# rapidshark-main-breakout-top-mk-1_9.net
KiCad netlist of a schematic drawn in EAGLE
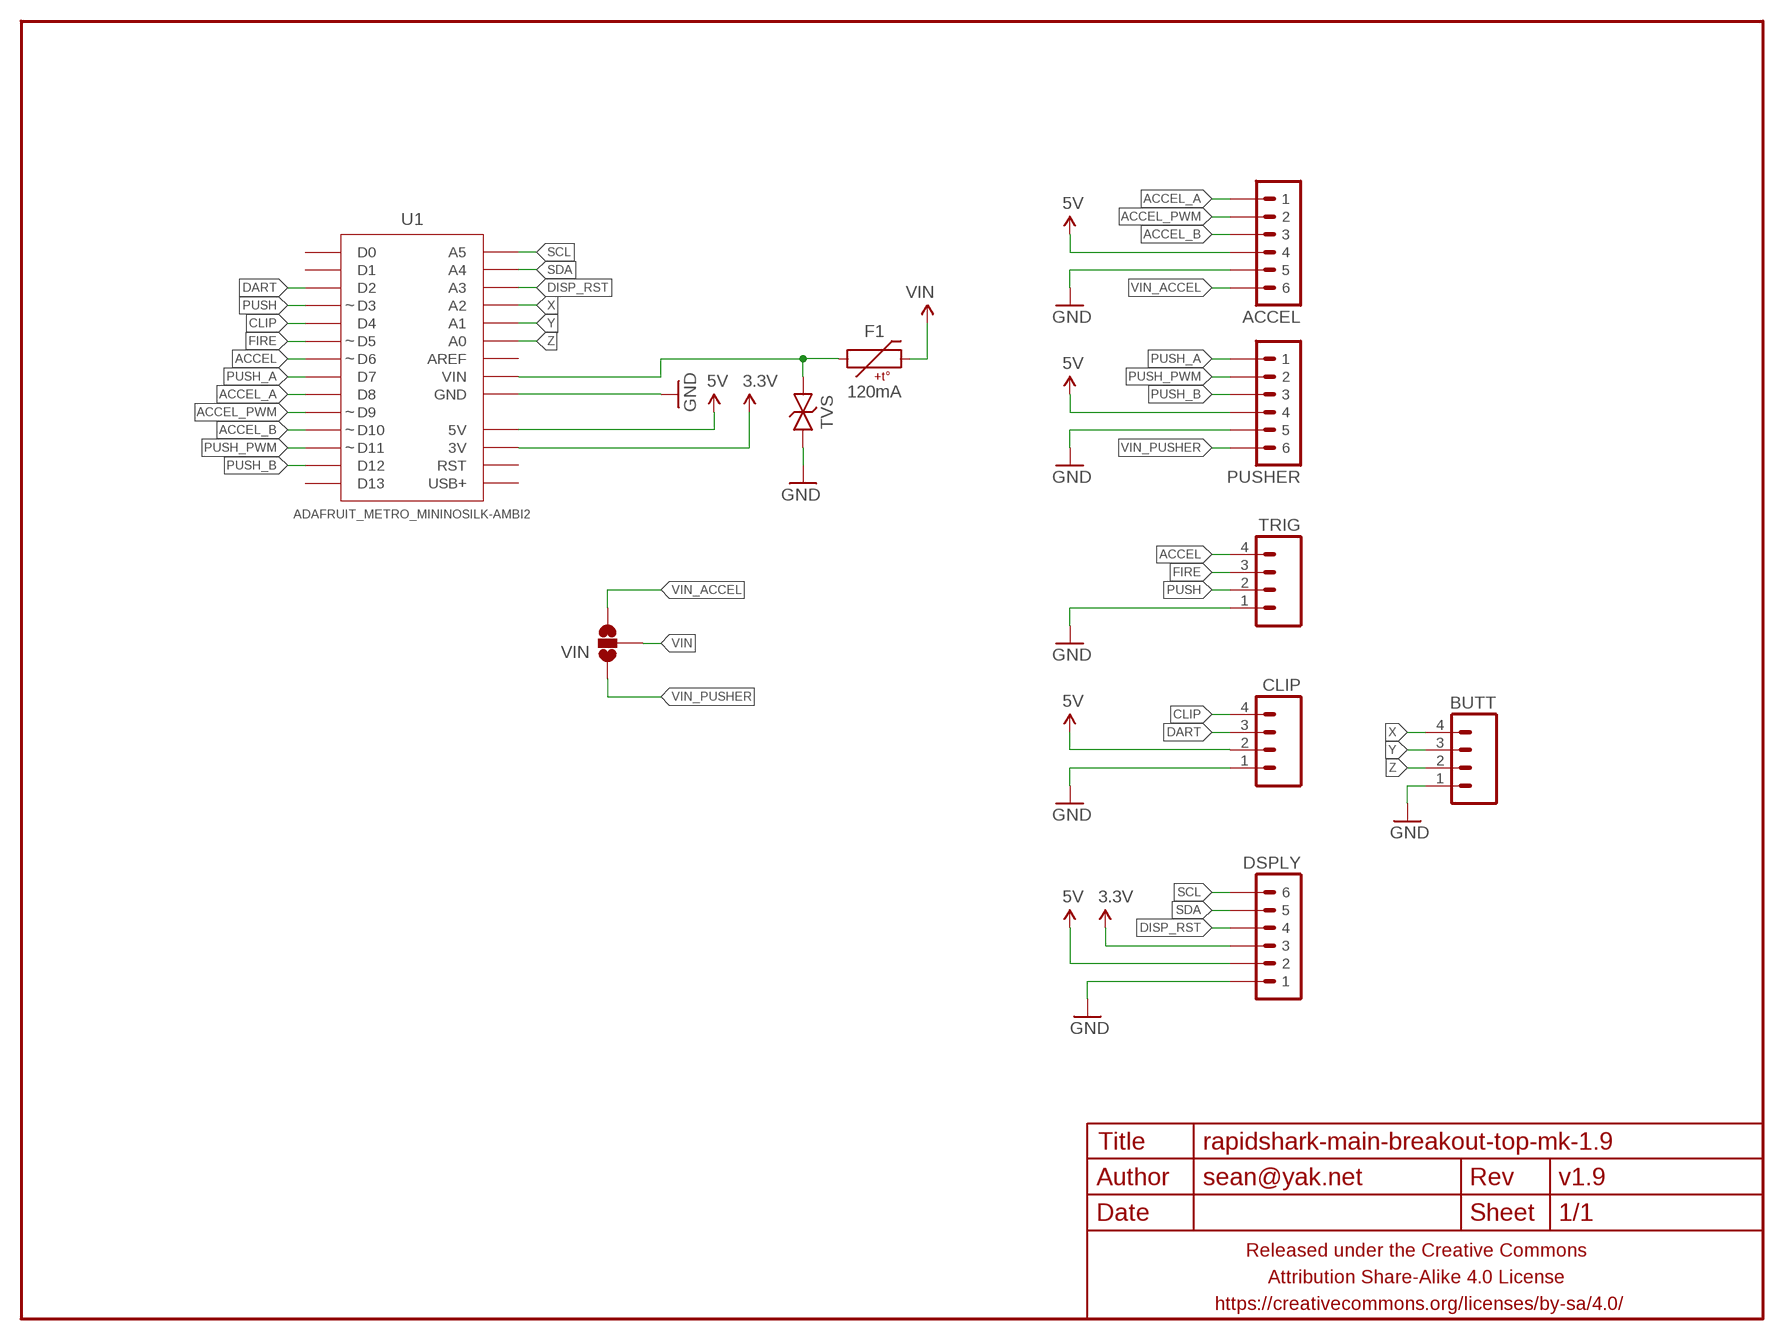
[diagram p0: schematic, sheet 1]

(export (version "E")
  (design (tool "Eeschema 10.0.6"))
  (components
    (comp (ref "ACCEL")
      (value "M06JST-PH-PTH-VERT")
      (footprint "eagle-import:JST-6-PH-VERT-PTH")
      (libsource (lib "eagle-import") (part "M06JST-PH-PTH-VERT"))
    )
    (comp (ref "BUTT")
      (value "M04JST-PTH-VERT")
      (footprint "eagle-import:JST-4-PH-VERT-PTH")
      (libsource (lib "eagle-import") (part "M04JST-PTH-VERT"))
    )
    (comp (ref "CLIP")
      (value "M04JST-PTH-VERT")
      (footprint "eagle-import:JST-4-PH-VERT-PTH")
      (libsource (lib "eagle-import") (part "M04JST-PTH-VERT"))
    )
    (comp (ref "DSPLY")
      (value "M06JST-PH-PTH-VERT")
      (footprint "eagle-import:JST-6-PH-VERT-PTH")
      (libsource (lib "eagle-import") (part "M06JST-PH-PTH-VERT"))
    )
    (comp (ref "F1")
      (value "120mA")
      (footprint "eagle-import:PTC-1206")
      (libsource (lib "eagle-import") (part "PTCSMD"))
    )
    (comp (ref "FRAME1")
      (value "FRAME-LETTERNO_PACKAGE")
      (footprint "eagle-import:DUMMY")
      (fields (field (name "DESIGNER") "sean@yak.net") (field (name "VERSION") "v1.9"))
      (libsource (lib "eagle-import") (part "FRAME-LETTERNO_PACKAGE"))
    )
    (comp (ref "PUSHER")
      (value "M06JST-PH-PTH-VERT")
      (footprint "eagle-import:JST-6-PH-VERT-PTH")
      (libsource (lib "eagle-import") (part "M06JST-PH-PTH-VERT"))
    )
    (comp (ref "TRIG")
      (value "M04JST-PTH-VERT")
      (footprint "eagle-import:JST-4-PH-VERT-PTH")
      (libsource (lib "eagle-import") (part "M04JST-PTH-VERT"))
    )
    (comp (ref "TVS")
      (value "TVSSMA")
      (footprint "eagle-import:SMA-DIODE-TVS-BIDIR")
      (libsource (lib "eagle-import") (part "TVSSMA"))
    )
    (comp (ref "U1")
      (value "ADAFRUIT_METRO_MININOSILK-AMBI2")
      (footprint "eagle-import:ADAFRUIT_METRO_MINI_BACK")
      (libsource (lib "eagle-import") (part "ADAFRUIT_METRO_MININOSILK-AMBI2"))
    )
    (comp (ref "VIN")
      (value "JUMPER-PAD-3-NOFULL_BOX_SILK")
      (footprint "eagle-import:PAD-JUMPER-3-NO_YES_SILK_FULL_BOX")
      (libsource (lib "eagle-import") (part "JUMPER-PAD-3-NOFULL_BOX_SILK"))
    )
  )
  (nets
    (net (code "1") (name "3.3V") (class "Default")
      (node (ref "DSPLY") (pin "3") (pinfunction "3_3") (pintype "passive"))
      (node (ref "U1") (pin "17") (pinfunction "3V_17") (pintype "bidirectional"))
    )
    (net (code "2") (name "5V") (class "Default")
      (node (ref "ACCEL") (pin "4") (pinfunction "4_4") (pintype "passive"))
      (node (ref "CLIP") (pin "2") (pinfunction "2_2") (pintype "passive"))
      (node (ref "DSPLY") (pin "2") (pinfunction "2_2") (pintype "passive"))
      (node (ref "PUSHER") (pin "4") (pinfunction "4_4") (pintype "passive"))
      (node (ref "U1") (pin "18") (pinfunction "5V_18") (pintype "bidirectional"))
    )
    (net (code "3") (name "ACCEL") (class "Default")
      (node (ref "TRIG") (pin "4") (pinfunction "4_4") (pintype "passive"))
      (node (ref "U1") (pin "7") (pinfunction "D6_7") (pintype "bidirectional"))
    )
    (net (code "4") (name "ACCEL_A") (class "Default")
      (node (ref "ACCEL") (pin "1") (pinfunction "1_1") (pintype "passive"))
      (node (ref "U1") (pin "9") (pinfunction "D8_9") (pintype "bidirectional"))
    )
    (net (code "5") (name "ACCEL_B") (class "Default")
      (node (ref "ACCEL") (pin "3") (pinfunction "3_3") (pintype "passive"))
      (node (ref "U1") (pin "11") (pinfunction "D10_11") (pintype "bidirectional"))
    )
    (net (code "6") (name "ACCEL_PWM") (class "Default")
      (node (ref "ACCEL") (pin "2") (pinfunction "2_2") (pintype "passive"))
      (node (ref "U1") (pin "10") (pinfunction "D9_10") (pintype "bidirectional"))
    )
    (net (code "7") (name "CLIP") (class "Default")
      (node (ref "CLIP") (pin "4") (pinfunction "4_4") (pintype "passive"))
      (node (ref "U1") (pin "5") (pinfunction "D4_5") (pintype "bidirectional"))
    )
    (net (code "8") (name "DART") (class "Default")
      (node (ref "CLIP") (pin "3") (pinfunction "3_3") (pintype "passive"))
      (node (ref "U1") (pin "3") (pinfunction "D2_3") (pintype "bidirectional"))
    )
    (net (code "9") (name "DISP_RST") (class "Default")
      (node (ref "DSPLY") (pin "4") (pinfunction "4_4") (pintype "passive"))
      (node (ref "U1") (pin "26") (pinfunction "A3_26") (pintype "bidirectional"))
    )
    (net (code "10") (name "FIRE") (class "Default")
      (node (ref "TRIG") (pin "3") (pinfunction "3_3") (pintype "passive"))
      (node (ref "U1") (pin "6") (pinfunction "D5_6") (pintype "bidirectional"))
    )
    (net (code "11") (name "GND") (class "Default")
      (node (ref "ACCEL") (pin "5") (pinfunction "5_5") (pintype "passive"))
      (node (ref "BUTT") (pin "1") (pinfunction "1_1") (pintype "passive"))
      (node (ref "CLIP") (pin "1") (pinfunction "1_1") (pintype "passive"))
      (node (ref "DSPLY") (pin "1") (pinfunction "1_1") (pintype "passive"))
      (node (ref "PUSHER") (pin "5") (pinfunction "5_5") (pintype "passive"))
      (node (ref "TRIG") (pin "1") (pinfunction "1_1") (pintype "passive"))
      (node (ref "TVS") (pin "1") (pinfunction "1_1") (pintype "passive"))
      (node (ref "U1") (pin "19") (pinfunction "GND_19") (pintype "bidirectional"))
      (node (ref "U1") (pin "20") (pinfunction "GND_20") (pintype "bidirectional"))
    )
    (net (code "12") (name "Net-(U1-VIN)") (class "Default")
      (node (ref "F1") (pin "1") (pinfunction "1_1") (pintype "passive"))
      (node (ref "TVS") (pin "2") (pinfunction "2_2") (pintype "passive"))
      (node (ref "U1") (pin "21") (pinfunction "VIN_21") (pintype "bidirectional"))
    )
    (net (code "13") (name "PUSH") (class "Default")
      (node (ref "TRIG") (pin "2") (pinfunction "2_2") (pintype "passive"))
      (node (ref "U1") (pin "4") (pinfunction "D3_4") (pintype "bidirectional"))
    )
    (net (code "14") (name "PUSH_A") (class "Default")
      (node (ref "PUSHER") (pin "1") (pinfunction "1_1") (pintype "passive"))
      (node (ref "U1") (pin "8") (pinfunction "D7_8") (pintype "bidirectional"))
    )
    (net (code "15") (name "PUSH_B") (class "Default")
      (node (ref "PUSHER") (pin "3") (pinfunction "3_3") (pintype "passive"))
      (node (ref "U1") (pin "13") (pinfunction "D12_13") (pintype "bidirectional"))
    )
    (net (code "16") (name "PUSH_PWM") (class "Default")
      (node (ref "PUSHER") (pin "2") (pinfunction "2_2") (pintype "passive"))
      (node (ref "U1") (pin "12") (pinfunction "D11_12") (pintype "bidirectional"))
    )
    (net (code "17") (name "SCL") (class "Default")
      (node (ref "DSPLY") (pin "6") (pinfunction "6_6") (pintype "passive"))
      (node (ref "U1") (pin "28") (pinfunction "A5_28") (pintype "bidirectional"))
    )
    (net (code "18") (name "SDA") (class "Default")
      (node (ref "DSPLY") (pin "5") (pinfunction "5_5") (pintype "passive"))
      (node (ref "U1") (pin "27") (pinfunction "A4_27") (pintype "bidirectional"))
    )
    (net (code "19") (name "VIN") (class "Default")
      (node (ref "F1") (pin "2") (pinfunction "2_2") (pintype "passive"))
      (node (ref "VIN") (pin "2") (pinfunction "2_2") (pintype "passive"))
    )
    (net (code "20") (name "VIN_ACCEL") (class "Default")
      (node (ref "ACCEL") (pin "6") (pinfunction "6_6") (pintype "passive"))
      (node (ref "VIN") (pin "3") (pinfunction "3_3") (pintype "passive"))
    )
    (net (code "21") (name "VIN_PUSHER") (class "Default")
      (node (ref "PUSHER") (pin "6") (pinfunction "6_6") (pintype "passive"))
      (node (ref "VIN") (pin "1") (pinfunction "1_1") (pintype "passive"))
    )
    (net (code "22") (name "X") (class "Default")
      (node (ref "BUTT") (pin "4") (pinfunction "4_4") (pintype "passive"))
      (node (ref "U1") (pin "25") (pinfunction "A2_25") (pintype "bidirectional"))
    )
    (net (code "23") (name "Y") (class "Default")
      (node (ref "BUTT") (pin "3") (pinfunction "3_3") (pintype "passive"))
      (node (ref "U1") (pin "24") (pinfunction "A1_24") (pintype "bidirectional"))
    )
    (net (code "24") (name "Z") (class "Default")
      (node (ref "BUTT") (pin "2") (pinfunction "2_2") (pintype "passive"))
      (node (ref "U1") (pin "23") (pinfunction "A0_23") (pintype "bidirectional"))
    )
    (net (code "25") (name "unconnected-(U1-AREF-Pad22)") (class "Default")
      (node (ref "U1") (pin "22") (pinfunction "AREF_22") (pintype "bidirectional"))
    )
    (net (code "26") (name "unconnected-(U1-D0-Pad1)") (class "Default")
      (node (ref "U1") (pin "1") (pinfunction "D0_1") (pintype "bidirectional"))
    )
    (net (code "27") (name "unconnected-(U1-D1-Pad2)") (class "Default")
      (node (ref "U1") (pin "2") (pinfunction "D1_2") (pintype "bidirectional"))
    )
    (net (code "28") (name "unconnected-(U1-D13-Pad14)") (class "Default")
      (node (ref "U1") (pin "14") (pinfunction "D13_14") (pintype "bidirectional"))
    )
    (net (code "29") (name "unconnected-(U1-RST-Pad16)") (class "Default")
      (node (ref "U1") (pin "16") (pinfunction "RST_16") (pintype "bidirectional"))
    )
    (net (code "30") (name "unconnected-(U1-USB+-Pad15)") (class "Default")
      (node (ref "U1") (pin "15") (pinfunction "USB+_15") (pintype "bidirectional"))
    )
  )
)
